# BAT.net
KiCad netlist of a schematic drawn in Altium Designer
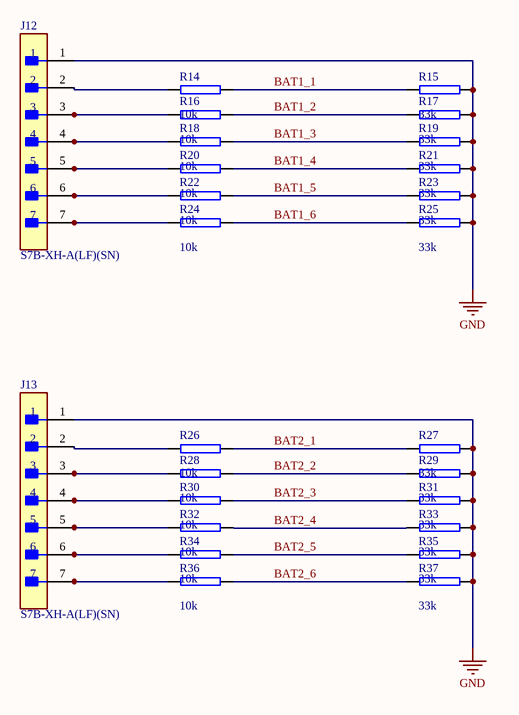
[diagram p0: BAT.SchDoc]

(export (version "E")
  (design (tool "Eeschema 10.0.6"))
  (components
    (comp (ref "J12")
      (value "S7B-XH-A(LF)(SN)")
      (footprint "FP-S7B-XH-A_LF_SN-MFG")
      (description "CONN HEADER R/A 7POS 2.5MM")
      (libsource (lib "Altium Content Vault") (part "5bcee6b94e1fee4be3f4cc3a650a442"))
    )
    (comp (ref "J13")
      (value "S7B-XH-A(LF)(SN)")
      (footprint "FP-S7B-XH-A_LF_SN-MFG")
      (description "CONN HEADER R/A 7POS 2.5MM")
      (libsource (lib "Altium Content Vault") (part "5bcee6b94e1fee4be3f4cc3a650a442"))
    )
    (comp (ref "R14")
      (value "10k")
      (footprint "0805")
      (fields (field (name "TOLERANCE") "1%") (field (name "Comment") "R 10K 0805"))
      (libsource (lib "FHGR_Altium_database") (part "Resistor"))
    )
    (comp (ref "R15")
      (value "33k")
      (footprint "0805")
      (fields (field (name "TOLERANCE") "1%") (field (name "Comment") "R 33K 0805"))
      (libsource (lib "FHGR_Altium_database") (part "Resistor"))
    )
    (comp (ref "R16")
      (value "10k")
      (footprint "0805")
      (fields (field (name "TOLERANCE") "1%") (field (name "Comment") "R 10K 0805"))
      (libsource (lib "FHGR_Altium_database") (part "Resistor"))
    )
    (comp (ref "R17")
      (value "33k")
      (footprint "0805")
      (fields (field (name "TOLERANCE") "1%") (field (name "Comment") "R 33K 0805"))
      (libsource (lib "FHGR_Altium_database") (part "Resistor"))
    )
    (comp (ref "R18")
      (value "10k")
      (footprint "0805")
      (fields (field (name "TOLERANCE") "1%") (field (name "Comment") "R 10K 0805"))
      (libsource (lib "FHGR_Altium_database") (part "Resistor"))
    )
    (comp (ref "R19")
      (value "33k")
      (footprint "0805")
      (fields (field (name "TOLERANCE") "1%") (field (name "Comment") "R 33K 0805"))
      (libsource (lib "FHGR_Altium_database") (part "Resistor"))
    )
    (comp (ref "R20")
      (value "10k")
      (footprint "0805")
      (fields (field (name "TOLERANCE") "1%") (field (name "Comment") "R 10K 0805"))
      (libsource (lib "FHGR_Altium_database") (part "Resistor"))
    )
    (comp (ref "R21")
      (value "33k")
      (footprint "0805")
      (fields (field (name "TOLERANCE") "1%") (field (name "Comment") "R 33K 0805"))
      (libsource (lib "FHGR_Altium_database") (part "Resistor"))
    )
    (comp (ref "R22")
      (value "10k")
      (footprint "0805")
      (fields (field (name "TOLERANCE") "1%") (field (name "Comment") "R 10K 0805"))
      (libsource (lib "FHGR_Altium_database") (part "Resistor"))
    )
    (comp (ref "R23")
      (value "33k")
      (footprint "0805")
      (fields (field (name "TOLERANCE") "1%") (field (name "Comment") "R 33K 0805"))
      (libsource (lib "FHGR_Altium_database") (part "Resistor"))
    )
    (comp (ref "R24")
      (value "10k")
      (footprint "0805")
      (fields (field (name "TOLERANCE") "1%") (field (name "Comment") "R 10K 0805"))
      (libsource (lib "FHGR_Altium_database") (part "Resistor"))
    )
    (comp (ref "R25")
      (value "33k")
      (footprint "0805")
      (fields (field (name "TOLERANCE") "1%") (field (name "Comment") "R 33K 0805"))
      (libsource (lib "FHGR_Altium_database") (part "Resistor"))
    )
    (comp (ref "R26")
      (value "10k")
      (footprint "0805")
      (fields (field (name "TOLERANCE") "1%") (field (name "Comment") "R 10K 0805"))
      (libsource (lib "FHGR_Altium_database") (part "Resistor"))
    )
    (comp (ref "R27")
      (value "33k")
      (footprint "0805")
      (fields (field (name "TOLERANCE") "1%") (field (name "Comment") "R 33K 0805"))
      (libsource (lib "FHGR_Altium_database") (part "Resistor"))
    )
    (comp (ref "R28")
      (value "10k")
      (footprint "0805")
      (fields (field (name "TOLERANCE") "1%") (field (name "Comment") "R 10K 0805"))
      (libsource (lib "FHGR_Altium_database") (part "Resistor"))
    )
    (comp (ref "R29")
      (value "33k")
      (footprint "0805")
      (fields (field (name "TOLERANCE") "1%") (field (name "Comment") "R 33K 0805"))
      (libsource (lib "FHGR_Altium_database") (part "Resistor"))
    )
    (comp (ref "R30")
      (value "10k")
      (footprint "0805")
      (fields (field (name "TOLERANCE") "1%") (field (name "Comment") "R 10K 0805"))
      (libsource (lib "FHGR_Altium_database") (part "Resistor"))
    )
    (comp (ref "R31")
      (value "33k")
      (footprint "0805")
      (fields (field (name "TOLERANCE") "1%") (field (name "Comment") "R 33K 0805"))
      (libsource (lib "FHGR_Altium_database") (part "Resistor"))
    )
    (comp (ref "R32")
      (value "10k")
      (footprint "0805")
      (fields (field (name "TOLERANCE") "1%") (field (name "Comment") "R 10K 0805"))
      (libsource (lib "FHGR_Altium_database") (part "Resistor"))
    )
    (comp (ref "R33")
      (value "33k")
      (footprint "0805")
      (fields (field (name "TOLERANCE") "1%") (field (name "Comment") "R 33K 0805"))
      (libsource (lib "FHGR_Altium_database") (part "Resistor"))
    )
    (comp (ref "R34")
      (value "10k")
      (footprint "0805")
      (fields (field (name "TOLERANCE") "1%") (field (name "Comment") "R 10K 0805"))
      (libsource (lib "FHGR_Altium_database") (part "Resistor"))
    )
    (comp (ref "R35")
      (value "33k")
      (footprint "0805")
      (fields (field (name "TOLERANCE") "1%") (field (name "Comment") "R 33K 0805"))
      (libsource (lib "FHGR_Altium_database") (part "Resistor"))
    )
    (comp (ref "R36")
      (value "10k")
      (footprint "0805")
      (fields (field (name "TOLERANCE") "1%") (field (name "Comment") "R 10K 0805"))
      (libsource (lib "FHGR_Altium_database") (part "Resistor"))
    )
    (comp (ref "R37")
      (value "33k")
      (footprint "0805")
      (fields (field (name "TOLERANCE") "1%") (field (name "Comment") "R 33K 0805"))
      (libsource (lib "FHGR_Altium_database") (part "Resistor"))
    )
  )
  (nets
    (net (code "1") (name "/BAT1_1") (class "Default")
      (node (ref "R14") (pin "2") (pintype "passive"))
      (node (ref "R15") (pin "1") (pintype "passive"))
    )
    (net (code "2") (name "/BAT1_2") (class "Default")
      (node (ref "R16") (pin "2") (pintype "passive"))
      (node (ref "R17") (pin "1") (pintype "passive"))
    )
    (net (code "3") (name "/BAT1_3") (class "Default")
      (node (ref "R18") (pin "2") (pintype "passive"))
      (node (ref "R19") (pin "1") (pintype "passive"))
    )
    (net (code "4") (name "/BAT1_4") (class "Default")
      (node (ref "R20") (pin "2") (pintype "passive"))
      (node (ref "R21") (pin "1") (pintype "passive"))
    )
    (net (code "5") (name "/BAT1_5") (class "Default")
      (node (ref "R22") (pin "2") (pintype "passive"))
      (node (ref "R23") (pin "1") (pintype "passive"))
    )
    (net (code "6") (name "/BAT1_6") (class "Default")
      (node (ref "R24") (pin "2") (pintype "passive"))
      (node (ref "R25") (pin "1") (pintype "passive"))
    )
    (net (code "7") (name "/BAT2_1") (class "Default")
      (node (ref "R26") (pin "2") (pintype "passive"))
      (node (ref "R27") (pin "1") (pintype "passive"))
    )
    (net (code "8") (name "/BAT2_2") (class "Default")
      (node (ref "R28") (pin "2") (pintype "passive"))
      (node (ref "R29") (pin "1") (pintype "passive"))
    )
    (net (code "9") (name "/BAT2_3") (class "Default")
      (node (ref "R30") (pin "2") (pintype "passive"))
      (node (ref "R31") (pin "1") (pintype "passive"))
    )
    (net (code "10") (name "/BAT2_4") (class "Default")
      (node (ref "R32") (pin "2") (pintype "passive"))
      (node (ref "R33") (pin "1") (pintype "passive"))
    )
    (net (code "11") (name "/BAT2_5") (class "Default")
      (node (ref "R34") (pin "2") (pintype "passive"))
      (node (ref "R35") (pin "1") (pintype "passive"))
    )
    (net (code "12") (name "/BAT2_6") (class "Default")
      (node (ref "R36") (pin "2") (pintype "passive"))
      (node (ref "R37") (pin "1") (pintype "passive"))
    )
    (net (code "13") (name "GND") (class "Default")
      (node (ref "J12") (pin "1") (pinfunction "1_1") (pintype "passive"))
      (node (ref "J13") (pin "1") (pinfunction "1_1") (pintype "passive"))
      (node (ref "R15") (pin "2") (pintype "passive"))
      (node (ref "R17") (pin "2") (pintype "passive"))
      (node (ref "R19") (pin "2") (pintype "passive"))
      (node (ref "R21") (pin "2") (pintype "passive"))
      (node (ref "R23") (pin "2") (pintype "passive"))
      (node (ref "R25") (pin "2") (pintype "passive"))
      (node (ref "R27") (pin "2") (pintype "passive"))
      (node (ref "R29") (pin "2") (pintype "passive"))
      (node (ref "R31") (pin "2") (pintype "passive"))
      (node (ref "R33") (pin "2") (pintype "passive"))
      (node (ref "R35") (pin "2") (pintype "passive"))
      (node (ref "R37") (pin "2") (pintype "passive"))
    )
    (net (code "14") (name "Net-(J12-Pad2)") (class "Default")
      (node (ref "J12") (pin "2") (pinfunction "2_2") (pintype "passive"))
      (node (ref "R14") (pin "1") (pintype "passive"))
    )
    (net (code "15") (name "Net-(J12-Pad3)") (class "Default")
      (node (ref "J12") (pin "3") (pinfunction "3_3") (pintype "passive"))
      (node (ref "R16") (pin "1") (pintype "passive"))
    )
    (net (code "16") (name "Net-(J12-Pad4)") (class "Default")
      (node (ref "J12") (pin "4") (pinfunction "4_4") (pintype "passive"))
      (node (ref "R18") (pin "1") (pintype "passive"))
    )
    (net (code "17") (name "Net-(J12-Pad5)") (class "Default")
      (node (ref "J12") (pin "5") (pinfunction "5_5") (pintype "passive"))
      (node (ref "R20") (pin "1") (pintype "passive"))
    )
    (net (code "18") (name "Net-(J12-Pad6)") (class "Default")
      (node (ref "J12") (pin "6") (pinfunction "6_6") (pintype "passive"))
      (node (ref "R22") (pin "1") (pintype "passive"))
    )
    (net (code "19") (name "Net-(J12-Pad7)") (class "Default")
      (node (ref "J12") (pin "7") (pinfunction "7_7") (pintype "passive"))
      (node (ref "R24") (pin "1") (pintype "passive"))
    )
    (net (code "20") (name "Net-(J13-Pad2)") (class "Default")
      (node (ref "J13") (pin "2") (pinfunction "2_2") (pintype "passive"))
      (node (ref "R26") (pin "1") (pintype "passive"))
    )
    (net (code "21") (name "Net-(J13-Pad3)") (class "Default")
      (node (ref "J13") (pin "3") (pinfunction "3_3") (pintype "passive"))
      (node (ref "R28") (pin "1") (pintype "passive"))
    )
    (net (code "22") (name "Net-(J13-Pad4)") (class "Default")
      (node (ref "J13") (pin "4") (pinfunction "4_4") (pintype "passive"))
      (node (ref "R30") (pin "1") (pintype "passive"))
    )
    (net (code "23") (name "Net-(J13-Pad5)") (class "Default")
      (node (ref "J13") (pin "5") (pinfunction "5_5") (pintype "passive"))
      (node (ref "R32") (pin "1") (pintype "passive"))
    )
    (net (code "24") (name "Net-(J13-Pad6)") (class "Default")
      (node (ref "J13") (pin "6") (pinfunction "6_6") (pintype "passive"))
      (node (ref "R34") (pin "1") (pintype "passive"))
    )
    (net (code "25") (name "Net-(J13-Pad7)") (class "Default")
      (node (ref "J13") (pin "7") (pinfunction "7_7") (pintype "passive"))
      (node (ref "R36") (pin "1") (pintype "passive"))
    )
  )
)
